# resistive_splitter.net
KiCad netlist of a schematic drawn in EAGLE
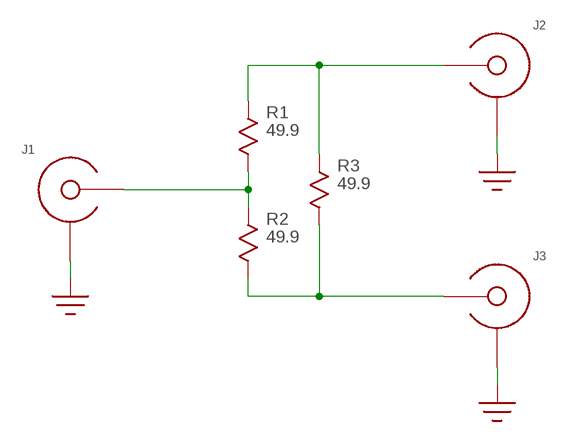
[diagram p0: schematic, sheet 1]

(export (version "E")
  (design (tool "Eeschema 10.0.6"))
  (components
    (comp (ref "J1")
      (value "EDGE_LAUNCH_JACKNARROW")
      (footprint "eagle-import:EDGE_LAUNCH_RF_CON_NARROW")
      (libsource (lib "eagle-import") (part "EDGE_LAUNCH_JACKNARROW"))
    )
    (comp (ref "J2")
      (value "EDGE_LAUNCH_JACKNARROW")
      (footprint "eagle-import:EDGE_LAUNCH_RF_CON_NARROW")
      (libsource (lib "eagle-import") (part "EDGE_LAUNCH_JACKNARROW"))
    )
    (comp (ref "J3")
      (value "EDGE_LAUNCH_JACKNARROW")
      (footprint "eagle-import:EDGE_LAUNCH_RF_CON_NARROW")
      (libsource (lib "eagle-import") (part "EDGE_LAUNCH_JACKNARROW"))
    )
    (comp (ref "R1")
      (value "49.9")
      (footprint "eagle-import:R0603")
      (libsource (lib "eagle-import") (part "R0603"))
    )
    (comp (ref "R2")
      (value "49.9")
      (footprint "eagle-import:R0603")
      (libsource (lib "eagle-import") (part "R0603"))
    )
    (comp (ref "R3")
      (value "49.9")
      (footprint "eagle-import:R0603")
      (libsource (lib "eagle-import") (part "R0603"))
    )
  )
  (nets
    (net (code "1") (name "GND") (class "Default")
      (node (ref "J1") (pin "GND@1") (pinfunction "SHIELD_GND@1") (pintype "bidirectional"))
      (node (ref "J1") (pin "GND@2") (pinfunction "SHIELD_GND@2") (pintype "bidirectional"))
      (node (ref "J1") (pin "GND@3") (pinfunction "SHIELD_GND@3") (pintype "bidirectional"))
      (node (ref "J1") (pin "GND@4") (pinfunction "SHIELD_GND@4") (pintype "bidirectional"))
      (node (ref "J1") (pin "GND@5") (pinfunction "SHIELD_GND@5") (pintype "bidirectional"))
      (node (ref "J1") (pin "GND@6") (pinfunction "SHIELD_GND@6") (pintype "bidirectional"))
      (node (ref "J1") (pin "SHIELD@1") (pinfunction "SHIELD_SHIELD@1") (pintype "bidirectional"))
      (node (ref "J1") (pin "SHIELD@2") (pinfunction "SHIELD_SHIELD@2") (pintype "bidirectional"))
      (node (ref "J2") (pin "GND@1") (pinfunction "SHIELD_GND@1") (pintype "bidirectional"))
      (node (ref "J2") (pin "GND@2") (pinfunction "SHIELD_GND@2") (pintype "bidirectional"))
      (node (ref "J2") (pin "GND@3") (pinfunction "SHIELD_GND@3") (pintype "bidirectional"))
      (node (ref "J2") (pin "GND@4") (pinfunction "SHIELD_GND@4") (pintype "bidirectional"))
      (node (ref "J2") (pin "GND@5") (pinfunction "SHIELD_GND@5") (pintype "bidirectional"))
      (node (ref "J2") (pin "GND@6") (pinfunction "SHIELD_GND@6") (pintype "bidirectional"))
      (node (ref "J2") (pin "SHIELD@1") (pinfunction "SHIELD_SHIELD@1") (pintype "bidirectional"))
      (node (ref "J2") (pin "SHIELD@2") (pinfunction "SHIELD_SHIELD@2") (pintype "bidirectional"))
      (node (ref "J3") (pin "GND@1") (pinfunction "SHIELD_GND@1") (pintype "bidirectional"))
      (node (ref "J3") (pin "GND@2") (pinfunction "SHIELD_GND@2") (pintype "bidirectional"))
      (node (ref "J3") (pin "GND@3") (pinfunction "SHIELD_GND@3") (pintype "bidirectional"))
      (node (ref "J3") (pin "GND@4") (pinfunction "SHIELD_GND@4") (pintype "bidirectional"))
      (node (ref "J3") (pin "GND@5") (pinfunction "SHIELD_GND@5") (pintype "bidirectional"))
      (node (ref "J3") (pin "GND@6") (pinfunction "SHIELD_GND@6") (pintype "bidirectional"))
      (node (ref "J3") (pin "SHIELD@1") (pinfunction "SHIELD_SHIELD@1") (pintype "bidirectional"))
      (node (ref "J3") (pin "SHIELD@2") (pinfunction "SHIELD_SHIELD@2") (pintype "bidirectional"))
    )
    (net (code "2") (name "Net-(R1-P$3)") (class "Default")
      (node (ref "J2") (pin "CENTER") (pinfunction "CENTER_CENTER") (pintype "bidirectional"))
      (node (ref "R1") (pin "P$1") (pinfunction "P$3_P$1") (pintype "bidirectional"))
      (node (ref "R3") (pin "P$1") (pinfunction "P$3_P$1") (pintype "bidirectional"))
    )
    (net (code "3") (name "Net-(R1-P$4)") (class "Default")
      (node (ref "J1") (pin "CENTER") (pinfunction "CENTER_CENTER") (pintype "bidirectional"))
      (node (ref "R1") (pin "P$2") (pinfunction "P$4_P$2") (pintype "bidirectional"))
      (node (ref "R2") (pin "P$1") (pinfunction "P$3_P$1") (pintype "bidirectional"))
    )
    (net (code "4") (name "Net-(R2-P$4)") (class "Default")
      (node (ref "J3") (pin "CENTER") (pinfunction "CENTER_CENTER") (pintype "bidirectional"))
      (node (ref "R2") (pin "P$2") (pinfunction "P$4_P$2") (pintype "bidirectional"))
      (node (ref "R3") (pin "P$2") (pinfunction "P$4_P$2") (pintype "bidirectional"))
    )
  )
)
